# encodeur_rotor_rpm.net
KiCad netlist of a schematic drawn in Altium Designer
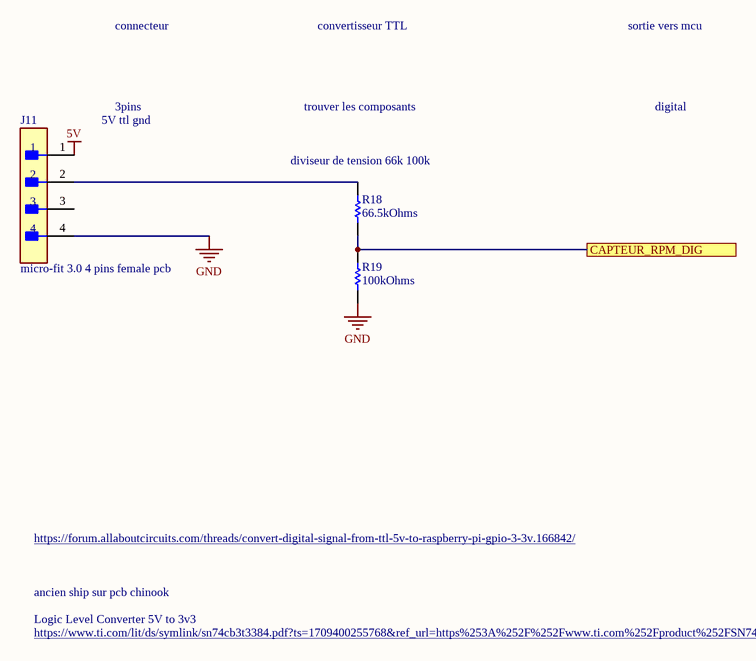
[diagram p0: encodeur_rotor_rpm.SchDoc]

(export (version "E")
  (design (tool "Eeschema 10.0.6"))
  (components
    (comp (ref "J11")
      (value "micro-fit 3.0 4 pins female pcb")
      (footprint "FP-43045-0400-MFG")
      (description "MOLEX 43045-0400 Header, Dual Row, 90°, 4p, Tin Plating Snap-in Peg PCB Lock, GW Compatible")
      (fields (field (name "MANUFACTURER") "Molex") (field (name "MANUFACTURER PART NUMBER") "43045-0400"))
      (libsource (lib "chinook_lib_symbol_rotor") (part "430450400"))
    )
    (comp (ref "R18")
      (value "66.5kOhms")
      (footprint "RESC1005X40X25LL05T10")
      (description "SMD Chip Resistor, 66.5 kOhm, ± 1%, 63 mW, 0402 [1005 Metric], Thick Film, General Purpose")
      (fields
        (field (name "MANUFACTURER") "Yageo")
        (field (name "MANUFACTURER PART NUMBER") "RC0402FR-0766K5L")
      )
      (libsource (lib "chinook_lib_symbol_rotor") (part "RC0402FR-0766K5L"))
    )
    (comp (ref "R19")
      (value "100kOhms")
      (footprint "RESC1005X40X25NL05T10")
      (description "SMD Chip Resistor, 100 kOhm, ± 1%, 63 mW, 0402 [1005 Metric], Thick Film, General Purpose")
      (fields
        (field (name "MANUFACTURER") "Yageo")
        (field (name "MANUFACTURER PART NUMBER") "RC0402FR-07100KL")
      )
      (libsource (lib "chinook_lib_symbol_rotor") (part "RC0402FR-07100KL"))
    )
  )
  (nets
    (net (code "1") (name "/CAPTEUR_RPM_DIG") (class "Default")
      (node (ref "R18") (pin "1") (pinfunction "1_1") (pintype "passive"))
      (node (ref "R19") (pin "2") (pinfunction "2_2") (pintype "passive"))
    )
    (net (code "2") (name "5V") (class "Default")
      (node (ref "J11") (pin "1") (pinfunction "1_1") (pintype "passive"))
    )
    (net (code "3") (name "GND") (class "Default")
      (node (ref "J11") (pin "4") (pinfunction "4_4") (pintype "passive"))
      (node (ref "R19") (pin "1") (pinfunction "1_1") (pintype "passive"))
    )
    (net (code "4") (name "Net-(J11-Pad2)") (class "Default")
      (node (ref "J11") (pin "2") (pinfunction "2_2") (pintype "passive"))
      (node (ref "R18") (pin "2") (pinfunction "2_2") (pintype "passive"))
    )
    (net (code "5") (name "unconnected-(J11-Pad3)") (class "Default")
      (node (ref "J11") (pin "3") (pinfunction "3_3") (pintype "passive"))
    )
  )
)
